# eeZeeTiny841.net
KiCad netlist of a schematic drawn in EAGLE
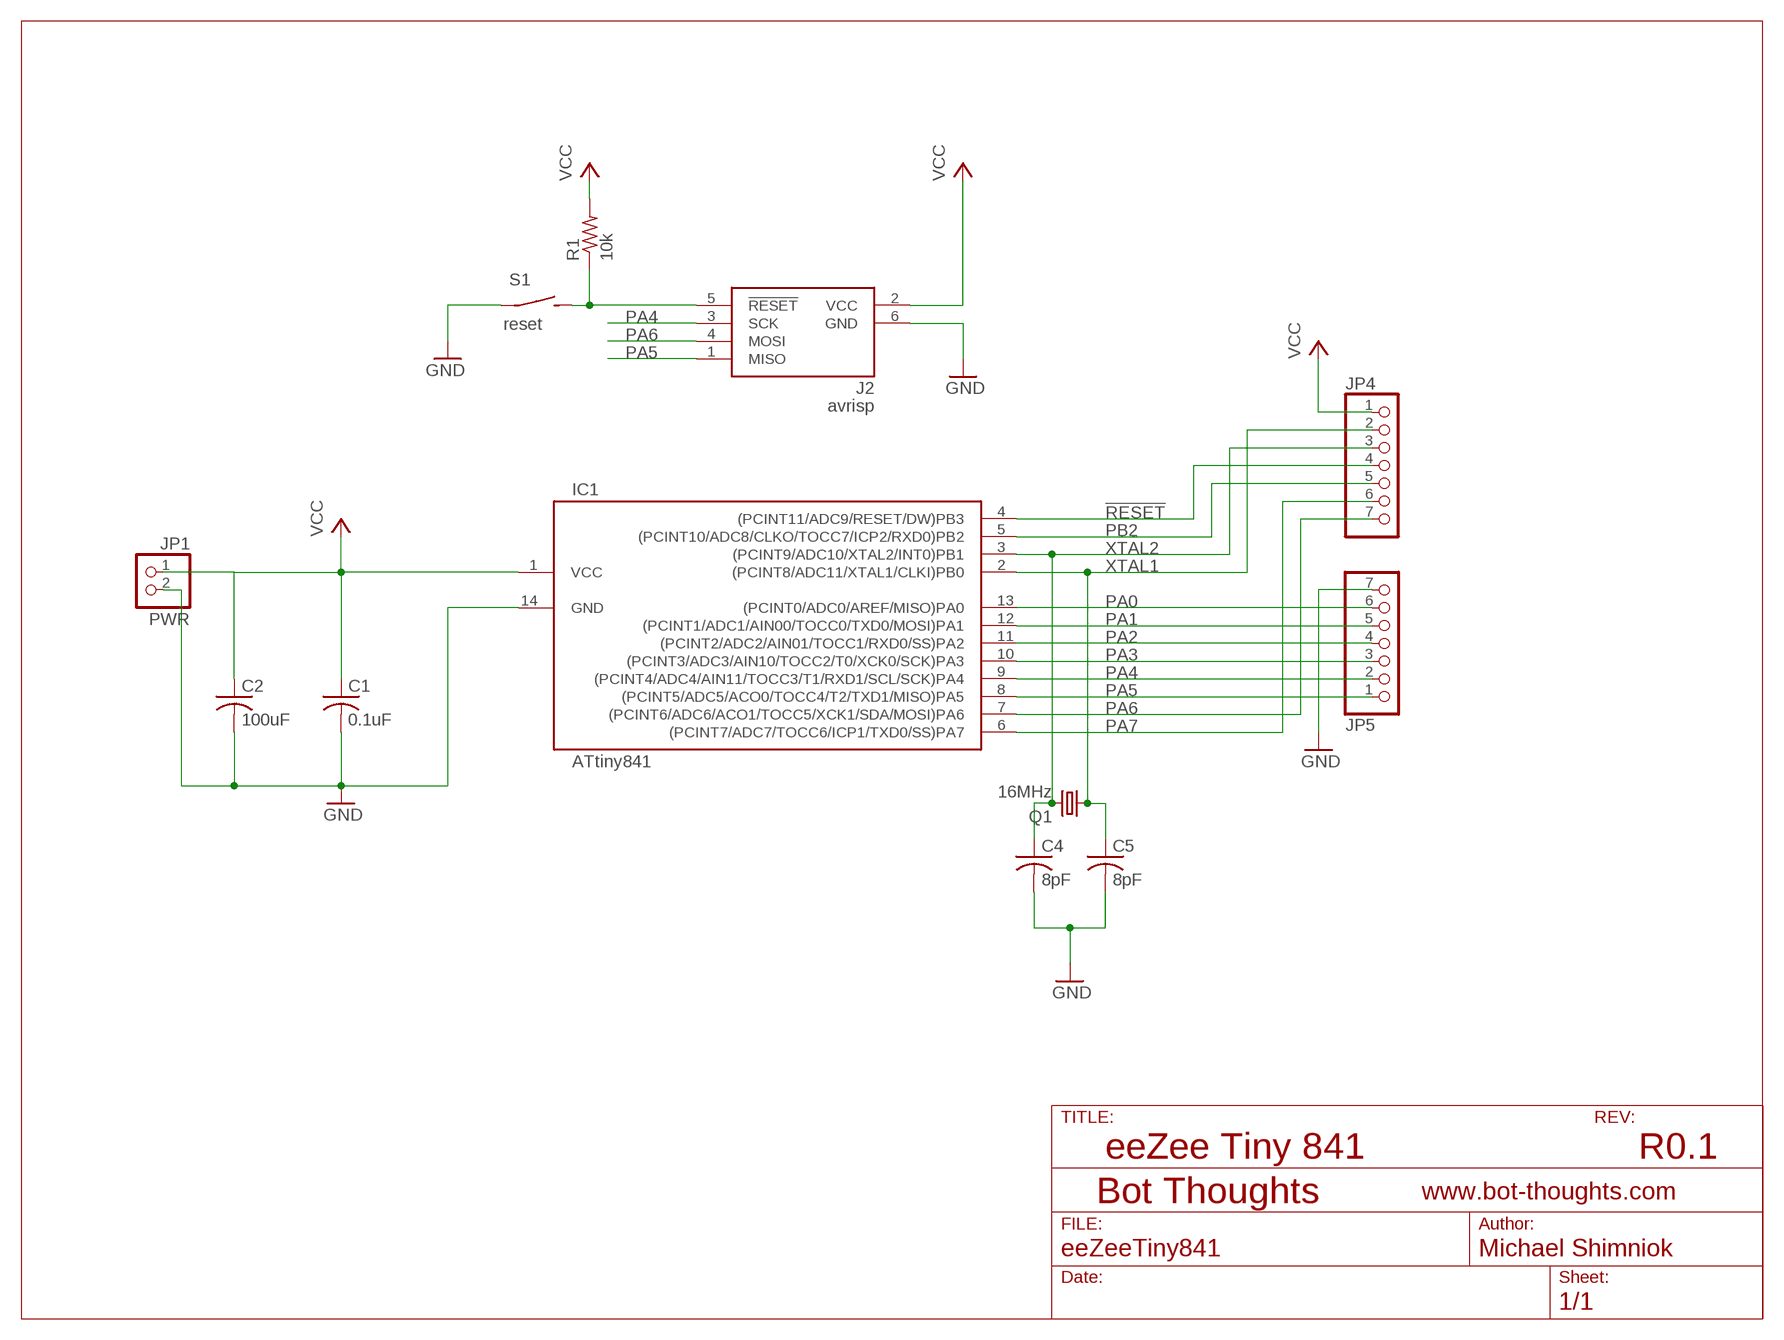
[diagram p0: schematic, sheet 1]

(export (version "E")
  (design (tool "Eeschema 10.0.6"))
  (components
    (comp (ref "C1")
      (value "0.1uF")
      (footprint "eagle-import:C0603")
      (fields (field (name "PARTNO") "0603YC104KAT2A"))
      (libsource (lib "eagle-import") (part "C-USC0603"))
    )
    (comp (ref "C2")
      (value "100uF")
      (footprint "eagle-import:C1206")
      (fields (field (name "PARTNO") "MCTT21X106M6R3CT"))
      (libsource (lib "eagle-import") (part "C-USC1206"))
    )
    (comp (ref "C4")
      (value "8pF")
      (footprint "eagle-import:C0603")
      (fields (field (name "PARTNO") "0603YC104KAT2A"))
      (libsource (lib "eagle-import") (part "C-USC0603"))
    )
    (comp (ref "C5")
      (value "8pF")
      (footprint "eagle-import:C0603")
      (fields (field (name "PARTNO") "0603YC104KAT2A"))
      (libsource (lib "eagle-import") (part "C-USC0603"))
    )
    (comp (ref "IC1")
      (value "ATtiny841")
      (footprint "eagle-import:14SOICN")
      (libsource (lib "eagle-import") (part "ATTINY441/841-SSU"))
    )
    (comp (ref "J2")
      (value "avrisp")
      (footprint "eagle-import:CON6P2R")
      (libsource (lib "eagle-import") (part "AVRISP6_COMPACT"))
    )
    (comp (ref "JP1")
      (value "PWR")
      (footprint "eagle-import:1X02-S")
      (libsource (lib "eagle-import") (part "PINHD-1X02_2.54-S"))
    )
    (comp (ref "JP4")
      (value "PINHD-1X07_2.54-S")
      (footprint "eagle-import:1X07-S")
      (libsource (lib "eagle-import") (part "PINHD-1X07_2.54-S"))
    )
    (comp (ref "JP5")
      (value "PINHD-1X07_2.54-S")
      (footprint "eagle-import:1X07-S")
      (libsource (lib "eagle-import") (part "PINHD-1X07_2.54-S"))
    )
    (comp (ref "Q1")
      (value "16MHz")
      (footprint "eagle-import:NDK_2PAD_5X3")
      (libsource (lib "eagle-import") (part "CRYSTALNDK5X3"))
    )
    (comp (ref "R1")
      (value "10k")
      (footprint "eagle-import:R0603")
      (fields (field (name "PARTNO") "ERJ-3GEYJ103V"))
      (libsource (lib "eagle-import") (part "R-US_R0603"))
    )
    (comp (ref "S1")
      (value "reset")
      (footprint "eagle-import:6MMTACTILE_RECT")
      (libsource (lib "eagle-import") (part "SPST_TAC_RECT1"))
    )
  )
  (nets
    (net (code "1") (name "/PA0") (class "Default")
      (node (ref "IC1") (pin "13") (pinfunction "(PCINT0/ADC0/AREF/MISO)PA0_13") (pintype "bidirectional"))
      (node (ref "JP5") (pin "6") (pinfunction "6_6") (pintype "passive"))
    )
    (net (code "2") (name "/PA1") (class "Default")
      (node (ref "IC1") (pin "12") (pinfunction "(PCINT1/ADC1/AIN00/TOCC0/TXD0/MOSI)PA1_12") (pintype "bidirectional"))
      (node (ref "JP5") (pin "5") (pinfunction "5_5") (pintype "passive"))
    )
    (net (code "3") (name "/PA2") (class "Default")
      (node (ref "IC1") (pin "11") (pinfunction "(PCINT2/ADC2/AIN01/TOCC1/RXD0/SS)PA2_11") (pintype "bidirectional"))
      (node (ref "JP5") (pin "4") (pinfunction "4_4") (pintype "passive"))
    )
    (net (code "4") (name "/PA3") (class "Default")
      (node (ref "IC1") (pin "10") (pinfunction "(PCINT3/ADC3/AIN10/TOCC2/T0/XCK0/SCK)PA3_10") (pintype "bidirectional"))
      (node (ref "JP5") (pin "3") (pinfunction "3_3") (pintype "passive"))
    )
    (net (code "5") (name "/PA4") (class "Default")
      (node (ref "IC1") (pin "9") (pinfunction "(PCINT4/ADC4/AIN11/TOCC3/T1/RXD1/SCL/SCK)PA4_9") (pintype "bidirectional"))
      (node (ref "J2") (pin "3") (pinfunction "SCK_3") (pintype "output"))
      (node (ref "JP5") (pin "2") (pinfunction "2_2") (pintype "passive"))
    )
    (net (code "6") (name "/PA5") (class "Default")
      (node (ref "IC1") (pin "8") (pinfunction "(PCINT5/ADC5/ACO0/TOCC4/T2/TXD1/MISO)PA5_8") (pintype "bidirectional"))
      (node (ref "J2") (pin "1") (pinfunction "MISO_1") (pintype "input"))
      (node (ref "JP5") (pin "1") (pinfunction "1_1") (pintype "passive"))
    )
    (net (code "7") (name "/PA6") (class "Default")
      (node (ref "IC1") (pin "7") (pinfunction "(PCINT6/ADC6/ACO1/TOCC5/XCK1/SDA/MOSI)PA6_7") (pintype "bidirectional"))
      (node (ref "J2") (pin "4") (pinfunction "MOSI_4") (pintype "output"))
      (node (ref "JP4") (pin "7") (pinfunction "7_7") (pintype "passive"))
    )
    (net (code "8") (name "/PA7") (class "Default")
      (node (ref "IC1") (pin "6") (pinfunction "(PCINT7/ADC7/TOCC6/ICP1/TXD0/SS)PA7_6") (pintype "bidirectional"))
      (node (ref "JP4") (pin "6") (pinfunction "6_6") (pintype "passive"))
    )
    (net (code "9") (name "/PB2") (class "Default")
      (node (ref "IC1") (pin "5") (pinfunction "(PCINT10/ADC8/CLKO/TOCC7/ICP2/RXD0)PB2_5") (pintype "bidirectional"))
      (node (ref "JP4") (pin "5") (pinfunction "5_5") (pintype "passive"))
    )
    (net (code "10") (name "/XTAL1") (class "Default")
      (node (ref "C5") (pin "1") (pinfunction "1_1") (pintype "passive"))
      (node (ref "IC1") (pin "2") (pinfunction "(PCINT8/ADC11/XTAL1/CLKI)PB0_2") (pintype "bidirectional"))
      (node (ref "JP4") (pin "2") (pinfunction "2_2") (pintype "passive"))
      (node (ref "Q1") (pin "P$1") (pinfunction "1_P$1") (pintype "passive"))
    )
    (net (code "11") (name "/XTAL2") (class "Default")
      (node (ref "C4") (pin "1") (pinfunction "1_1") (pintype "passive"))
      (node (ref "IC1") (pin "3") (pinfunction "(PCINT9/ADC10/XTAL2/INT0)PB1_3") (pintype "bidirectional"))
      (node (ref "JP4") (pin "3") (pinfunction "3_3") (pintype "passive"))
      (node (ref "Q1") (pin "P$2") (pinfunction "2_P$2") (pintype "passive"))
    )
    (net (code "12") (name "/~{RESET}") (class "Default")
      (node (ref "IC1") (pin "4") (pinfunction "(PCINT11/ADC9/RESET/DW)PB3_4") (pintype "bidirectional"))
      (node (ref "J2") (pin "5") (pinfunction "~{RESET}_5") (pintype "output"))
      (node (ref "JP4") (pin "4") (pinfunction "4_4") (pintype "passive"))
      (node (ref "R1") (pin "1") (pinfunction "1_1") (pintype "passive"))
      (node (ref "S1") (pin "P$2") (pinfunction "S_P$2") (pintype "passive"))
    )
    (net (code "13") (name "GND") (class "Default")
      (node (ref "C1") (pin "2") (pinfunction "2_2") (pintype "passive"))
      (node (ref "C2") (pin "2") (pinfunction "2_2") (pintype "passive"))
      (node (ref "C4") (pin "2") (pinfunction "2_2") (pintype "passive"))
      (node (ref "C5") (pin "2") (pinfunction "2_2") (pintype "passive"))
      (node (ref "IC1") (pin "14") (pinfunction "GND_14") (pintype "bidirectional"))
      (node (ref "J2") (pin "6") (pinfunction "GND_6") (pintype "power_in"))
      (node (ref "JP1") (pin "2") (pinfunction "2_2") (pintype "passive"))
      (node (ref "JP5") (pin "7") (pinfunction "7_7") (pintype "passive"))
      (node (ref "S1") (pin "P$1") (pinfunction "P_P$1") (pintype "passive"))
    )
    (net (code "14") (name "VCC") (class "Default")
      (node (ref "C1") (pin "1") (pinfunction "1_1") (pintype "passive"))
      (node (ref "C2") (pin "1") (pinfunction "1_1") (pintype "passive"))
      (node (ref "IC1") (pin "1") (pinfunction "VCC_1") (pintype "bidirectional"))
      (node (ref "J2") (pin "2") (pinfunction "VCC_2") (pintype "power_in"))
      (node (ref "JP1") (pin "1") (pinfunction "1_1") (pintype "passive"))
      (node (ref "JP4") (pin "1") (pinfunction "1_1") (pintype "passive"))
      (node (ref "R1") (pin "2") (pinfunction "2_2") (pintype "passive"))
    )
  )
)
